# DBL_165_SerialIn_Register.net
KiCad netlist of a schematic drawn in Altium Designer
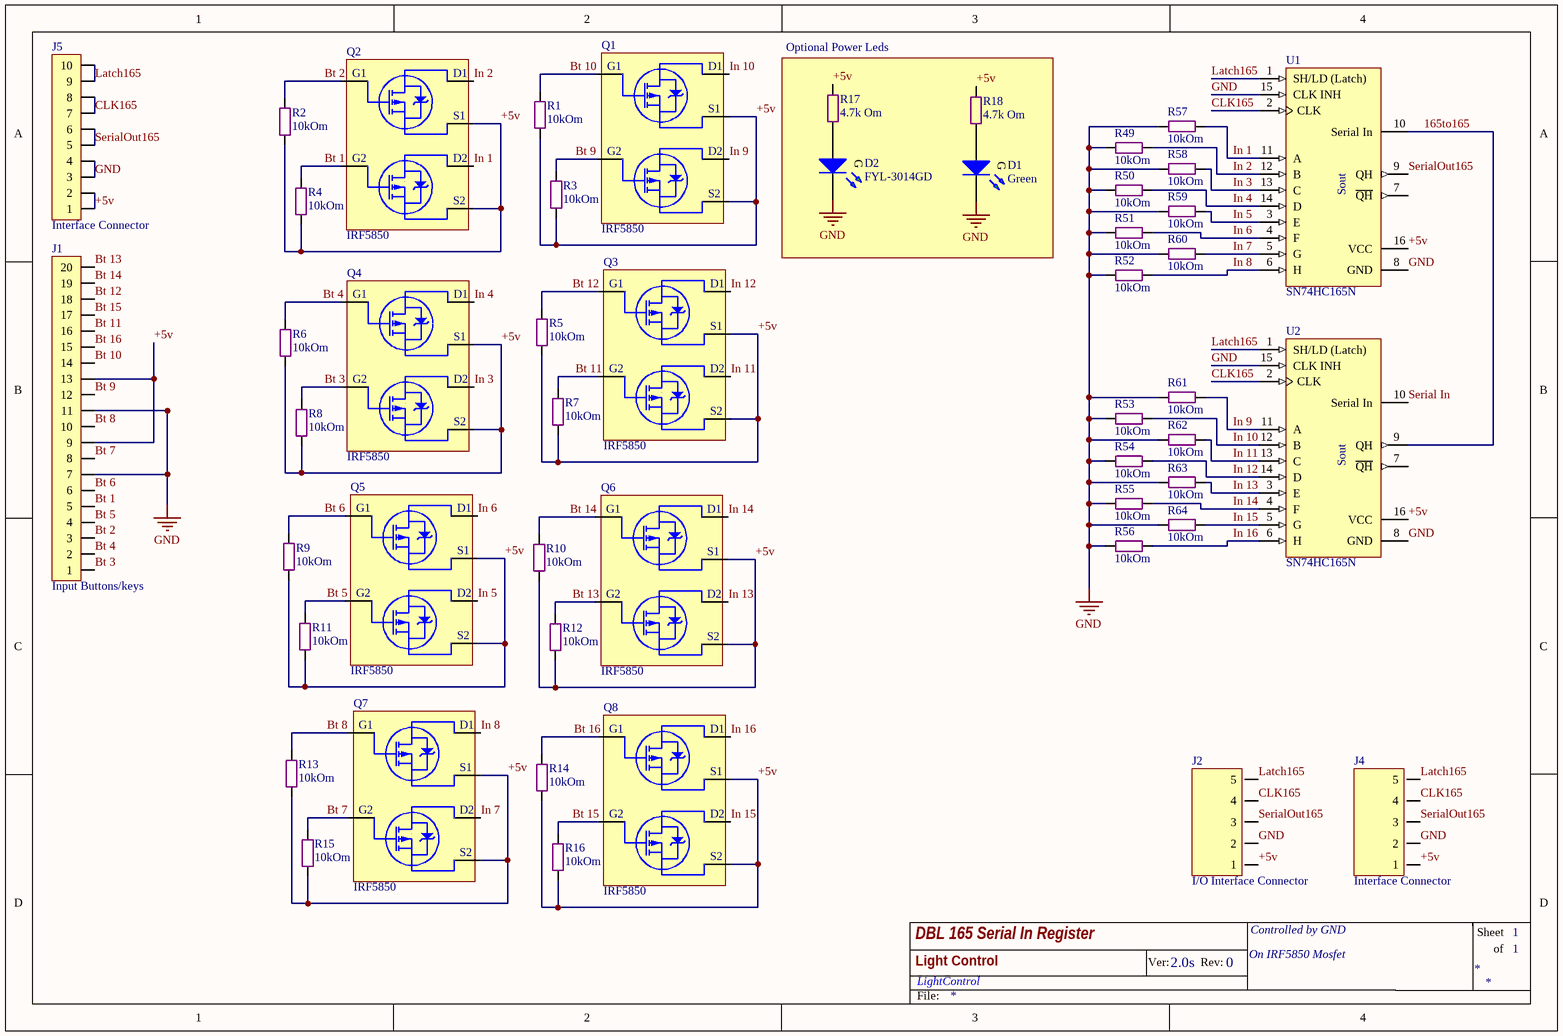
[diagram p0: DBL 165 SerialIn Register (v2).SchDoc]

(export (version "E")
  (design (tool "Eeschema 10.0.6"))
  (components
    (comp (ref "D1")
      (value "Green")
      (footprint "LED:LED SMD 0805 Green")
      (description "?2v ?20mA")
      (libsource (lib "LED") (part "Led SMD Green"))
    )
    (comp (ref "D2")
      (value "FYL-3014GD")
      (footprint "LED:LED Round 3mm Green")
      (description "2.1v 10mA, 15-30mCd")
      (libsource (lib "LED") (part "Led Round 3mm Green"))
    )
    (comp (ref "J1")
      (value "Input Buttons/keys")
      (footprint "Connector:LINE 2.54 x 20D (2 x 10) - BH")
      (description "Vert, Dbl line, Male")
      (libsource (lib "Connector") (part "PLD-20 (2 x 10)"))
    )
    (comp (ref "J2")
      (value "I/O Interface Connector")
      (footprint "Connector:Line 2.54 x 5")
      (description "Vert, Sgl line, Male")
      (libsource (lib "Connector") (part "PLS-5"))
    )
    (comp (ref "J4")
      (value "Interface Connector")
      (footprint "Connector:Line 2.54 x 5")
      (description "Vert, Sgl line, Male")
      (libsource (lib "Connector") (part "PLS-5"))
    )
    (comp (ref "J5")
      (value "Interface Connector")
      (footprint "Connector:LINE 2.54 x 10D (2 x 5) - BH")
      (description "Vert, Dbl line, Male")
      (libsource (lib "Connector") (part "PLD-10 (2 x 5)"))
    )
    (comp (ref "Q1")
      (value "IRF5850")
      (footprint "GeneralCases:TSOP-6")
      (description "Dual P-Ch  20V - 0.135Ω - 2.2A")
      (libsource (lib "Transistor") (part "IRF5850"))
    )
    (comp (ref "Q2")
      (value "IRF5850")
      (footprint "GeneralCases:TSOP-6")
      (description "Dual P-Ch  20V - 0.135Ω - 2.2A")
      (libsource (lib "Transistor") (part "IRF5850"))
    )
    (comp (ref "Q3")
      (value "IRF5850")
      (footprint "GeneralCases:TSOP-6")
      (description "Dual P-Ch  20V - 0.135Ω - 2.2A")
      (libsource (lib "Transistor") (part "IRF5850"))
    )
    (comp (ref "Q4")
      (value "IRF5850")
      (footprint "GeneralCases:TSOP-6")
      (description "Dual P-Ch  20V - 0.135Ω - 2.2A")
      (libsource (lib "Transistor") (part "IRF5850"))
    )
    (comp (ref "Q5")
      (value "IRF5850")
      (footprint "GeneralCases:TSOP-6")
      (description "Dual P-Ch  20V - 0.135Ω - 2.2A")
      (libsource (lib "Transistor") (part "IRF5850"))
    )
    (comp (ref "Q6")
      (value "IRF5850")
      (footprint "GeneralCases:TSOP-6")
      (description "Dual P-Ch  20V - 0.135Ω - 2.2A")
      (libsource (lib "Transistor") (part "IRF5850"))
    )
    (comp (ref "Q7")
      (value "IRF5850")
      (footprint "GeneralCases:TSOP-6")
      (description "Dual P-Ch  20V - 0.135Ω - 2.2A")
      (libsource (lib "Transistor") (part "IRF5850"))
    )
    (comp (ref "Q8")
      (value "IRF5850")
      (footprint "GeneralCases:TSOP-6")
      (description "Dual P-Ch  20V - 0.135Ω - 2.2A")
      (libsource (lib "Transistor") (part "IRF5850"))
    )
    (comp (ref "R1")
      (value "10kOm")
      (footprint "PassiveComponents:SMD 0805 (2012)")
      (libsource (lib "PassiveComponents") (part "Res All Types"))
    )
    (comp (ref "R2")
      (value "10kOm")
      (footprint "PassiveComponents:SMD 0805 (2012)")
      (libsource (lib "PassiveComponents") (part "Res All Types"))
    )
    (comp (ref "R3")
      (value "10kOm")
      (footprint "PassiveComponents:SMD 0805 (2012)")
      (libsource (lib "PassiveComponents") (part "Res All Types"))
    )
    (comp (ref "R4")
      (value "10kOm")
      (footprint "PassiveComponents:SMD 0805 (2012)")
      (libsource (lib "PassiveComponents") (part "Res All Types"))
    )
    (comp (ref "R5")
      (value "10kOm")
      (footprint "PassiveComponents:SMD 0805 (2012)")
      (libsource (lib "PassiveComponents") (part "Res All Types"))
    )
    (comp (ref "R6")
      (value "10kOm")
      (footprint "PassiveComponents:SMD 0805 (2012)")
      (libsource (lib "PassiveComponents") (part "Res All Types"))
    )
    (comp (ref "R7")
      (value "10kOm")
      (footprint "PassiveComponents:SMD 0805 (2012)")
      (libsource (lib "PassiveComponents") (part "Res All Types"))
    )
    (comp (ref "R8")
      (value "10kOm")
      (footprint "PassiveComponents:SMD 0805 (2012)")
      (libsource (lib "PassiveComponents") (part "Res All Types"))
    )
    (comp (ref "R9")
      (value "10kOm")
      (footprint "PassiveComponents:SMD 0805 (2012)")
      (libsource (lib "PassiveComponents") (part "Res All Types"))
    )
    (comp (ref "R10")
      (value "10kOm")
      (footprint "PassiveComponents:SMD 0805 (2012)")
      (libsource (lib "PassiveComponents") (part "Res All Types"))
    )
    (comp (ref "R11")
      (value "10kOm")
      (footprint "PassiveComponents:SMD 0805 (2012)")
      (libsource (lib "PassiveComponents") (part "Res All Types"))
    )
    (comp (ref "R12")
      (value "10kOm")
      (footprint "PassiveComponents:SMD 0805 (2012)")
      (libsource (lib "PassiveComponents") (part "Res All Types"))
    )
    (comp (ref "R13")
      (value "10kOm")
      (footprint "PassiveComponents:SMD 0805 (2012)")
      (libsource (lib "PassiveComponents") (part "Res All Types"))
    )
    (comp (ref "R14")
      (value "10kOm")
      (footprint "PassiveComponents:SMD 0805 (2012)")
      (libsource (lib "PassiveComponents") (part "Res All Types"))
    )
    (comp (ref "R15")
      (value "10kOm")
      (footprint "PassiveComponents:SMD 0805 (2012)")
      (libsource (lib "PassiveComponents") (part "Res All Types"))
    )
    (comp (ref "R16")
      (value "10kOm")
      (footprint "PassiveComponents:SMD 0805 (2012)")
      (libsource (lib "PassiveComponents") (part "Res All Types"))
    )
    (comp (ref "R17")
      (value "4.7k Om")
      (footprint "PassiveComponents:SMD 0805 (2012)")
      (libsource (lib "PassiveComponents") (part "Res All Types"))
    )
    (comp (ref "R18")
      (value "4.7k Om")
      (footprint "PassiveComponents:SMD 0805 (2012)")
      (libsource (lib "PassiveComponents") (part "Res All Types"))
    )
    (comp (ref "R49")
      (value "10kOm")
      (footprint "PassiveComponents:SMD 0805 (2012)")
      (libsource (lib "PassiveComponents") (part "Res All Types"))
    )
    (comp (ref "R50")
      (value "10kOm")
      (footprint "PassiveComponents:SMD 0805 (2012)")
      (libsource (lib "PassiveComponents") (part "Res All Types"))
    )
    (comp (ref "R51")
      (value "10kOm")
      (footprint "PassiveComponents:SMD 0805 (2012)")
      (libsource (lib "PassiveComponents") (part "Res All Types"))
    )
    (comp (ref "R52")
      (value "10kOm")
      (footprint "PassiveComponents:SMD 0805 (2012)")
      (libsource (lib "PassiveComponents") (part "Res All Types"))
    )
    (comp (ref "R53")
      (value "10kOm")
      (footprint "PassiveComponents:SMD 0805 (2012)")
      (libsource (lib "PassiveComponents") (part "Res All Types"))
    )
    (comp (ref "R54")
      (value "10kOm")
      (footprint "PassiveComponents:SMD 0805 (2012)")
      (libsource (lib "PassiveComponents") (part "Res All Types"))
    )
    (comp (ref "R55")
      (value "10kOm")
      (footprint "PassiveComponents:SMD 0805 (2012)")
      (libsource (lib "PassiveComponents") (part "Res All Types"))
    )
    (comp (ref "R56")
      (value "10kOm")
      (footprint "PassiveComponents:SMD 0805 (2012)")
      (libsource (lib "PassiveComponents") (part "Res All Types"))
    )
    (comp (ref "R57")
      (value "10kOm")
      (footprint "PassiveComponents:SMD 0805 (2012)")
      (libsource (lib "PassiveComponents") (part "Res All Types"))
    )
    (comp (ref "R58")
      (value "10kOm")
      (footprint "PassiveComponents:SMD 0805 (2012)")
      (libsource (lib "PassiveComponents") (part "Res All Types"))
    )
    (comp (ref "R59")
      (value "10kOm")
      (footprint "PassiveComponents:SMD 0805 (2012)")
      (libsource (lib "PassiveComponents") (part "Res All Types"))
    )
    (comp (ref "R60")
      (value "10kOm")
      (footprint "PassiveComponents:SMD 0805 (2012)")
      (libsource (lib "PassiveComponents") (part "Res All Types"))
    )
    (comp (ref "R61")
      (value "10kOm")
      (footprint "PassiveComponents:SMD 0805 (2012)")
      (libsource (lib "PassiveComponents") (part "Res All Types"))
    )
    (comp (ref "R62")
      (value "10kOm")
      (footprint "PassiveComponents:SMD 0805 (2012)")
      (libsource (lib "PassiveComponents") (part "Res All Types"))
    )
    (comp (ref "R63")
      (value "10kOm")
      (footprint "PassiveComponents:SMD 0805 (2012)")
      (libsource (lib "PassiveComponents") (part "Res All Types"))
    )
    (comp (ref "R64")
      (value "10kOm")
      (footprint "PassiveComponents:SMD 0805 (2012)")
      (libsource (lib "PassiveComponents") (part "Res All Types"))
    )
    (comp (ref "U1")
      (value "SN74HC165N")
      (footprint "GeneralCases:DIP-16")
      (description "8-Bit Parallel-Load Shift Register")
      (fields (field (name "PUBLISHER") "Altium Limited"))
      (libsource (lib "Chips") (part "SN74HC165N"))
    )
    (comp (ref "U2")
      (value "SN74HC165N")
      (footprint "GeneralCases:DIP-16")
      (description "8-Bit Parallel-Load Shift Register")
      (fields (field (name "PUBLISHER") "Altium Limited"))
      (libsource (lib "Chips") (part "SN74HC165N"))
    )
  )
  (nets
    (net (code "1") (name "/+5v") (class "Default")
      (node (ref "J1") (pin "13") (pinfunction "13_13") (pintype "passive"))
      (node (ref "J1") (pin "9") (pinfunction "9_9") (pintype "passive"))
      (node (ref "J2") (pin "1") (pinfunction "1_1") (pintype "passive"))
      (node (ref "J4") (pin "1") (pinfunction "1_1") (pintype "passive"))
      (node (ref "J5") (pin "1") (pinfunction "1_1") (pintype "passive"))
      (node (ref "J5") (pin "2") (pinfunction "2_2") (pintype "passive"))
      (node (ref "Q1") (pin "2") (pinfunction "S2_2") (pintype "passive"))
      (node (ref "Q1") (pin "5") (pinfunction "S1_5") (pintype "passive"))
      (node (ref "Q2") (pin "2") (pinfunction "S2_2") (pintype "passive"))
      (node (ref "Q2") (pin "5") (pinfunction "S1_5") (pintype "passive"))
      (node (ref "Q3") (pin "2") (pinfunction "S2_2") (pintype "passive"))
      (node (ref "Q3") (pin "5") (pinfunction "S1_5") (pintype "passive"))
      (node (ref "Q4") (pin "2") (pinfunction "S2_2") (pintype "passive"))
      (node (ref "Q4") (pin "5") (pinfunction "S1_5") (pintype "passive"))
      (node (ref "Q5") (pin "2") (pinfunction "S2_2") (pintype "passive"))
      (node (ref "Q5") (pin "5") (pinfunction "S1_5") (pintype "passive"))
      (node (ref "Q6") (pin "2") (pinfunction "S2_2") (pintype "passive"))
      (node (ref "Q6") (pin "5") (pinfunction "S1_5") (pintype "passive"))
      (node (ref "Q7") (pin "2") (pinfunction "S2_2") (pintype "passive"))
      (node (ref "Q7") (pin "5") (pinfunction "S1_5") (pintype "passive"))
      (node (ref "Q8") (pin "2") (pinfunction "S2_2") (pintype "passive"))
      (node (ref "Q8") (pin "5") (pinfunction "S1_5") (pintype "passive"))
      (node (ref "R1") (pin "2") (pinfunction "2_2") (pintype "passive"))
      (node (ref "R10") (pin "2") (pinfunction "2_2") (pintype "passive"))
      (node (ref "R11") (pin "2") (pinfunction "2_2") (pintype "passive"))
      (node (ref "R12") (pin "2") (pinfunction "2_2") (pintype "passive"))
      (node (ref "R13") (pin "2") (pinfunction "2_2") (pintype "passive"))
      (node (ref "R14") (pin "2") (pinfunction "2_2") (pintype "passive"))
      (node (ref "R15") (pin "2") (pinfunction "2_2") (pintype "passive"))
      (node (ref "R16") (pin "2") (pinfunction "2_2") (pintype "passive"))
      (node (ref "R17") (pin "1") (pinfunction "1_1") (pintype "passive"))
      (node (ref "R18") (pin "1") (pinfunction "1_1") (pintype "passive"))
      (node (ref "R2") (pin "2") (pinfunction "2_2") (pintype "passive"))
      (node (ref "R3") (pin "2") (pinfunction "2_2") (pintype "passive"))
      (node (ref "R4") (pin "2") (pinfunction "2_2") (pintype "passive"))
      (node (ref "R5") (pin "2") (pinfunction "2_2") (pintype "passive"))
      (node (ref "R6") (pin "2") (pinfunction "2_2") (pintype "passive"))
      (node (ref "R7") (pin "2") (pinfunction "2_2") (pintype "passive"))
      (node (ref "R8") (pin "2") (pinfunction "2_2") (pintype "passive"))
      (node (ref "R9") (pin "2") (pinfunction "2_2") (pintype "passive"))
      (node (ref "U1") (pin "16") (pinfunction "VCC_16") (pintype "power_in"))
      (node (ref "U2") (pin "16") (pinfunction "VCC_16") (pintype "power_in"))
    )
    (net (code "2") (name "/165to165") (class "Default")
      (node (ref "U1") (pin "10") (pinfunction "Serial_In_10") (pintype "passive"))
      (node (ref "U2") (pin "9") (pinfunction "QH_9") (pintype "output"))
    )
    (net (code "3") (name "/Bt 1") (class "Default")
      (node (ref "J1") (pin "5") (pinfunction "5_5") (pintype "passive"))
      (node (ref "Q2") (pin "3") (pinfunction "G2_3") (pintype "passive"))
      (node (ref "R4") (pin "1") (pinfunction "1_1") (pintype "passive"))
    )
    (net (code "4") (name "/Bt 2") (class "Default")
      (node (ref "J1") (pin "3") (pinfunction "3_3") (pintype "passive"))
      (node (ref "Q2") (pin "1") (pinfunction "G1_1") (pintype "passive"))
      (node (ref "R2") (pin "1") (pinfunction "1_1") (pintype "passive"))
    )
    (net (code "5") (name "/Bt 3") (class "Default")
      (node (ref "J1") (pin "1") (pinfunction "1_1") (pintype "passive"))
      (node (ref "Q4") (pin "3") (pinfunction "G2_3") (pintype "passive"))
      (node (ref "R8") (pin "1") (pinfunction "1_1") (pintype "passive"))
    )
    (net (code "6") (name "/Bt 4") (class "Default")
      (node (ref "J1") (pin "2") (pinfunction "2_2") (pintype "passive"))
      (node (ref "Q4") (pin "1") (pinfunction "G1_1") (pintype "passive"))
      (node (ref "R6") (pin "1") (pinfunction "1_1") (pintype "passive"))
    )
    (net (code "7") (name "/Bt 5") (class "Default")
      (node (ref "J1") (pin "4") (pinfunction "4_4") (pintype "passive"))
      (node (ref "Q5") (pin "3") (pinfunction "G2_3") (pintype "passive"))
      (node (ref "R11") (pin "1") (pinfunction "1_1") (pintype "passive"))
    )
    (net (code "8") (name "/Bt 6") (class "Default")
      (node (ref "J1") (pin "6") (pinfunction "6_6") (pintype "passive"))
      (node (ref "Q5") (pin "1") (pinfunction "G1_1") (pintype "passive"))
      (node (ref "R9") (pin "1") (pinfunction "1_1") (pintype "passive"))
    )
    (net (code "9") (name "/Bt 7") (class "Default")
      (node (ref "J1") (pin "8") (pinfunction "8_8") (pintype "passive"))
      (node (ref "Q7") (pin "3") (pinfunction "G2_3") (pintype "passive"))
      (node (ref "R15") (pin "1") (pinfunction "1_1") (pintype "passive"))
    )
    (net (code "10") (name "/Bt 8") (class "Default")
      (node (ref "J1") (pin "10") (pinfunction "10_10") (pintype "passive"))
      (node (ref "Q7") (pin "1") (pinfunction "G1_1") (pintype "passive"))
      (node (ref "R13") (pin "1") (pinfunction "1_1") (pintype "passive"))
    )
    (net (code "11") (name "/Bt 9") (class "Default")
      (node (ref "J1") (pin "12") (pinfunction "12_12") (pintype "passive"))
      (node (ref "Q1") (pin "3") (pinfunction "G2_3") (pintype "passive"))
      (node (ref "R3") (pin "1") (pinfunction "1_1") (pintype "passive"))
    )
    (net (code "12") (name "/Bt 10") (class "Default")
      (node (ref "J1") (pin "14") (pinfunction "14_14") (pintype "passive"))
      (node (ref "Q1") (pin "1") (pinfunction "G1_1") (pintype "passive"))
      (node (ref "R1") (pin "1") (pinfunction "1_1") (pintype "passive"))
    )
    (net (code "13") (name "/Bt 11") (class "Default")
      (node (ref "J1") (pin "16") (pinfunction "16_16") (pintype "passive"))
      (node (ref "Q3") (pin "3") (pinfunction "G2_3") (pintype "passive"))
      (node (ref "R7") (pin "1") (pinfunction "1_1") (pintype "passive"))
    )
    (net (code "14") (name "/Bt 12") (class "Default")
      (node (ref "J1") (pin "18") (pinfunction "18_18") (pintype "passive"))
      (node (ref "Q3") (pin "1") (pinfunction "G1_1") (pintype "passive"))
      (node (ref "R5") (pin "1") (pinfunction "1_1") (pintype "passive"))
    )
    (net (code "15") (name "/Bt 13") (class "Default")
      (node (ref "J1") (pin "20") (pinfunction "20_20") (pintype "passive"))
      (node (ref "Q6") (pin "3") (pinfunction "G2_3") (pintype "passive"))
      (node (ref "R12") (pin "1") (pinfunction "1_1") (pintype "passive"))
    )
    (net (code "16") (name "/Bt 14") (class "Default")
      (node (ref "J1") (pin "19") (pinfunction "19_19") (pintype "passive"))
      (node (ref "Q6") (pin "1") (pinfunction "G1_1") (pintype "passive"))
      (node (ref "R10") (pin "1") (pinfunction "1_1") (pintype "passive"))
    )
    (net (code "17") (name "/Bt 15") (class "Default")
      (node (ref "J1") (pin "17") (pinfunction "17_17") (pintype "passive"))
      (node (ref "Q8") (pin "3") (pinfunction "G2_3") (pintype "passive"))
      (node (ref "R16") (pin "1") (pinfunction "1_1") (pintype "passive"))
    )
    (net (code "18") (name "/Bt 16") (class "Default")
      (node (ref "J1") (pin "15") (pinfunction "15_15") (pintype "passive"))
      (node (ref "Q8") (pin "1") (pinfunction "G1_1") (pintype "passive"))
      (node (ref "R14") (pin "1") (pinfunction "1_1") (pintype "passive"))
    )
    (net (code "19") (name "/CLK165") (class "Default")
      (node (ref "J2") (pin "4") (pinfunction "4_4") (pintype "passive"))
      (node (ref "J4") (pin "4") (pinfunction "4_4") (pintype "passive"))
      (node (ref "J5") (pin "7") (pinfunction "7_7") (pintype "passive"))
      (node (ref "J5") (pin "8") (pinfunction "8_8") (pintype "passive"))
      (node (ref "U1") (pin "2") (pinfunction "CLK_2") (pintype "input"))
      (node (ref "U2") (pin "2") (pinfunction "CLK_2") (pintype "input"))
    )
    (net (code "20") (name "/In 1") (class "Default")
      (node (ref "Q2") (pin "4") (pinfunction "D2_4") (pintype "passive"))
      (node (ref "R57") (pin "2") (pinfunction "2_2") (pintype "passive"))
      (node (ref "U1") (pin "11") (pinfunction "A_11") (pintype "input"))
    )
    (net (code "21") (name "/In 2") (class "Default")
      (node (ref "Q2") (pin "6") (pinfunction "D1_6") (pintype "passive"))
      (node (ref "R49") (pin "2") (pinfunction "2_2") (pintype "passive"))
      (node (ref "U1") (pin "12") (pinfunction "B_12") (pintype "input"))
    )
    (net (code "22") (name "/In 3") (class "Default")
      (node (ref "Q4") (pin "4") (pinfunction "D2_4") (pintype "passive"))
      (node (ref "R58") (pin "2") (pinfunction "2_2") (pintype "passive"))
      (node (ref "U1") (pin "13") (pinfunction "C_13") (pintype "input"))
    )
    (net (code "23") (name "/In 4") (class "Default")
      (node (ref "Q4") (pin "6") (pinfunction "D1_6") (pintype "passive"))
      (node (ref "R50") (pin "2") (pinfunction "2_2") (pintype "passive"))
      (node (ref "U1") (pin "14") (pinfunction "D_14") (pintype "input"))
    )
    (net (code "24") (name "/In 5") (class "Default")
      (node (ref "Q5") (pin "4") (pinfunction "D2_4") (pintype "passive"))
      (node (ref "R59") (pin "2") (pinfunction "2_2") (pintype "passive"))
      (node (ref "U1") (pin "3") (pinfunction "E_3") (pintype "input"))
    )
    (net (code "25") (name "/In 6") (class "Default")
      (node (ref "Q5") (pin "6") (pinfunction "D1_6") (pintype "passive"))
      (node (ref "R51") (pin "2") (pinfunction "2_2") (pintype "passive"))
      (node (ref "U1") (pin "4") (pinfunction "F_4") (pintype "input"))
    )
    (net (code "26") (name "/In 7") (class "Default")
      (node (ref "Q7") (pin "4") (pinfunction "D2_4") (pintype "passive"))
      (node (ref "R60") (pin "2") (pinfunction "2_2") (pintype "passive"))
      (node (ref "U1") (pin "5") (pinfunction "G_5") (pintype "input"))
    )
    (net (code "27") (name "/In 8") (class "Default")
      (node (ref "Q7") (pin "6") (pinfunction "D1_6") (pintype "passive"))
      (node (ref "R52") (pin "2") (pinfunction "2_2") (pintype "passive"))
      (node (ref "U1") (pin "6") (pinfunction "H_6") (pintype "input"))
    )
    (net (code "28") (name "/In 9") (class "Default")
      (node (ref "Q1") (pin "4") (pinfunction "D2_4") (pintype "passive"))
      (node (ref "R61") (pin "2") (pinfunction "2_2") (pintype "passive"))
      (node (ref "U2") (pin "11") (pinfunction "A_11") (pintype "input"))
    )
    (net (code "29") (name "/In 10") (class "Default")
      (node (ref "Q1") (pin "6") (pinfunction "D1_6") (pintype "passive"))
      (node (ref "R53") (pin "2") (pinfunction "2_2") (pintype "passive"))
      (node (ref "U2") (pin "12") (pinfunction "B_12") (pintype "input"))
    )
    (net (code "30") (name "/In 11") (class "Default")
      (node (ref "Q3") (pin "4") (pinfunction "D2_4") (pintype "passive"))
      (node (ref "R62") (pin "2") (pinfunction "2_2") (pintype "passive"))
      (node (ref "U2") (pin "13") (pinfunction "C_13") (pintype "input"))
    )
    (net (code "31") (name "/In 12") (class "Default")
      (node (ref "Q3") (pin "6") (pinfunction "D1_6") (pintype "passive"))
      (node (ref "R54") (pin "2") (pinfunction "2_2") (pintype "passive"))
      (node (ref "U2") (pin "14") (pinfunction "D_14") (pintype "input"))
    )
    (net (code "32") (name "/In 13") (class "Default")
      (node (ref "Q6") (pin "4") (pinfunction "D2_4") (pintype "passive"))
      (node (ref "R63") (pin "2") (pinfunction "2_2") (pintype "passive"))
      (node (ref "U2") (pin "3") (pinfunction "E_3") (pintype "input"))
    )
    (net (code "33") (name "/In 14") (class "Default")
      (node (ref "Q6") (pin "6") (pinfunction "D1_6") (pintype "passive"))
      (node (ref "R55") (pin "2") (pinfunction "2_2") (pintype "passive"))
      (node (ref "U2") (pin "4") (pinfunction "F_4") (pintype "input"))
    )
    (net (code "34") (name "/In 15") (class "Default")
      (node (ref "Q8") (pin "4") (pinfunction "D2_4") (pintype "passive"))
      (node (ref "R64") (pin "2") (pinfunction "2_2") (pintype "passive"))
      (node (ref "U2") (pin "5") (pinfunction "G_5") (pintype "input"))
    )
    (net (code "35") (name "/In 16") (class "Default")
      (node (ref "Q8") (pin "6") (pinfunction "D1_6") (pintype "passive"))
      (node (ref "R56") (pin "2") (pinfunction "2_2") (pintype "passive"))
      (node (ref "U2") (pin "6") (pinfunction "H_6") (pintype "input"))
    )
    (net (code "36") (name "/Latch165") (class "Default")
      (node (ref "J2") (pin "5") (pinfunction "5_5") (pintype "passive"))
      (node (ref "J4") (pin "5") (pinfunction "5_5") (pintype "passive"))
      (node (ref "J5") (pin "10") (pinfunction "10_10") (pintype "passive"))
      (node (ref "J5") (pin "9") (pinfunction "9_9") (pintype "passive"))
      (node (ref "U1") (pin "1") (pinfunction "SH/LD_(Latch)_1") (pintype "input"))
      (node (ref "U2") (pin "1") (pinfunction "SH/LD_(Latch)_1") (pintype "input"))
    )
    (net (code "37") (name "/Serial In") (class "Default")
      (node (ref "U2") (pin "10") (pinfunction "Serial_In_10") (pintype "passive"))
    )
    (net (code "38") (name "/SerialOut165") (class "Default")
      (node (ref "J2") (pin "3") (pinfunction "3_3") (pintype "passive"))
      (node (ref "J4") (pin "3") (pinfunction "3_3") (pintype "passive"))
      (node (ref "J5") (pin "5") (pinfunction "5_5") (pintype "passive"))
      (node (ref "J5") (pin "6") (pinfunction "6_6") (pintype "passive"))
      (node (ref "U1") (pin "9") (pinfunction "QH_9") (pintype "output"))
    )
    (net (code "39") (name "GND") (class "Default")
      (node (ref "D1") (pin "K") (pinfunction "K_K") (pintype "passive"))
      (node (ref "D2") (pin "K") (pinfunction "K_K") (pintype "passive"))
      (node (ref "J1") (pin "11") (pinfunction "11_11") (pintype "passive"))
      (node (ref "J1") (pin "7") (pinfunction "7_7") (pintype "passive"))
      (node (ref "J2") (pin "2") (pinfunction "2_2") (pintype "passive"))
      (node (ref "J4") (pin "2") (pinfunction "2_2") (pintype "passive"))
      (node (ref "J5") (pin "3") (pinfunction "3_3") (pintype "passive"))
      (node (ref "J5") (pin "4") (pinfunction "4_4") (pintype "passive"))
      (node (ref "R49") (pin "1") (pinfunction "1_1") (pintype "passive"))
      (node (ref "R50") (pin "1") (pinfunction "1_1") (pintype "passive"))
      (node (ref "R51") (pin "1") (pinfunction "1_1") (pintype "passive"))
      (node (ref "R52") (pin "1") (pinfunction "1_1") (pintype "passive"))
      (node (ref "R53") (pin "1") (pinfunction "1_1") (pintype "passive"))
      (node (ref "R54") (pin "1") (pinfunction "1_1") (pintype "passive"))
      (node (ref "R55") (pin "1") (pinfunction "1_1") (pintype "passive"))
      (node (ref "R56") (pin "1") (pinfunction "1_1") (pintype "passive"))
      (node (ref "R57") (pin "1") (pinfunction "1_1") (pintype "passive"))
      (node (ref "R58") (pin "1") (pinfunction "1_1") (pintype "passive"))
      (node (ref "R59") (pin "1") (pinfunction "1_1") (pintype "passive"))
      (node (ref "R60") (pin "1") (pinfunction "1_1") (pintype "passive"))
      (node (ref "R61") (pin "1") (pinfunction "1_1") (pintype "passive"))
      (node (ref "R62") (pin "1") (pinfunction "1_1") (pintype "passive"))
      (node (ref "R63") (pin "1") (pinfunction "1_1") (pintype "passive"))
      (node (ref "R64") (pin "1") (pinfunction "1_1") (pintype "passive"))
      (node (ref "U1") (pin "15") (pinfunction "CLK_INH_15") (pintype "input"))
      (node (ref "U1") (pin "8") (pinfunction "GND_8") (pintype "power_in"))
      (node (ref "U2") (pin "15") (pinfunction "CLK_INH_15") (pintype "input"))
      (node (ref "U2") (pin "8") (pinfunction "GND_8") (pintype "power_in"))
    )
    (net (code "40") (name "Net-(D1-PadA)") (class "Default")
      (node (ref "D1") (pin "A") (pinfunction "A_A") (pintype "passive"))
      (node (ref "R18") (pin "2") (pinfunction "2_2") (pintype "passive"))
    )
    (net (code "41") (name "Net-(D2-PadA)") (class "Default")
      (node (ref "D2") (pin "A") (pinfunction "A_A") (pintype "passive"))
      (node (ref "R17") (pin "2") (pinfunction "2_2") (pintype "passive"))
    )
    (net (code "42") (name "unconnected-(U1-~{QH}-Pad7)") (class "Default")
      (node (ref "U1") (pin "7") (pinfunction "~{QH}_7") (pintype "output"))
    )
    (net (code "43") (name "unconnected-(U2-~{QH}-Pad7)") (class "Default")
      (node (ref "U2") (pin "7") (pinfunction "~{QH}_7") (pintype "output"))
    )
  )
)
